# CardController.net
KiCad netlist of a schematic drawn in EAGLE
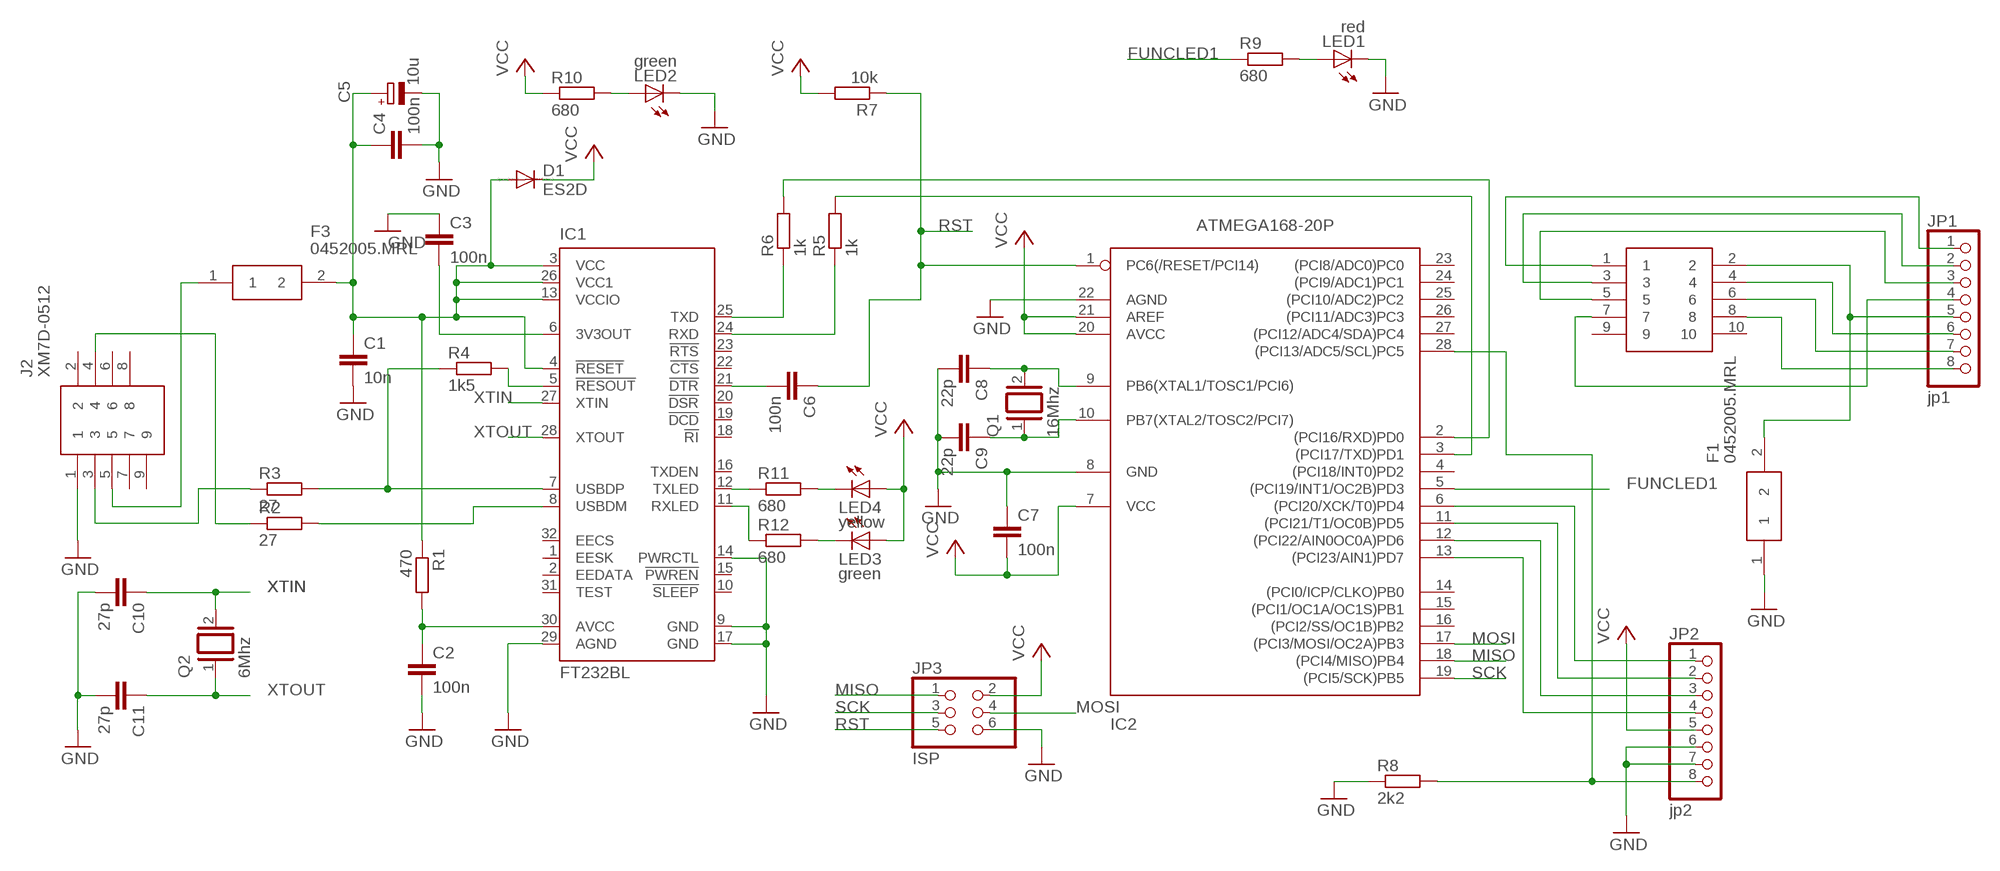
[diagram p0: schematic, sheet 1]

(export (version "E")
  (design (tool "Eeschema 10.0.6"))
  (components
    (comp (ref "C1")
      (value "10n")
      (footprint "eagle-import:C1206")
      (libsource (lib "eagle-import") (part "C-EUC1206"))
    )
    (comp (ref "C2")
      (value "100n")
      (footprint "eagle-import:C1206")
      (libsource (lib "eagle-import") (part "C-EUC1206"))
    )
    (comp (ref "C3")
      (value "100n")
      (footprint "eagle-import:C1206")
      (libsource (lib "eagle-import") (part "C-EUC1206"))
    )
    (comp (ref "C4")
      (value "100n")
      (footprint "eagle-import:C1206")
      (libsource (lib "eagle-import") (part "C-EUC1206"))
    )
    (comp (ref "C5")
      (value "10u")
      (footprint "eagle-import:B_3528-21W")
      (libsource (lib "eagle-import") (part "CPOL-EUB/3528-21W"))
    )
    (comp (ref "C6")
      (value "100n")
      (footprint "eagle-import:C1206")
      (libsource (lib "eagle-import") (part "C-EUC1206"))
    )
    (comp (ref "C7")
      (value "100n")
      (footprint "eagle-import:C1206")
      (libsource (lib "eagle-import") (part "C-EUC1206"))
    )
    (comp (ref "C8")
      (value "22p")
      (footprint "eagle-import:C1206")
      (libsource (lib "eagle-import") (part "C-EUC1206"))
    )
    (comp (ref "C9")
      (value "22p")
      (footprint "eagle-import:C1206")
      (libsource (lib "eagle-import") (part "C-EUC1206"))
    )
    (comp (ref "C10")
      (value "27p")
      (footprint "eagle-import:C1206")
      (libsource (lib "eagle-import") (part "C-EUC1206"))
    )
    (comp (ref "C11")
      (value "27p")
      (footprint "eagle-import:C1206")
      (libsource (lib "eagle-import") (part "C-EUC1206"))
    )
    (comp (ref "D1")
      (value "ES2D")
      (footprint "eagle-import:SMB")
      (libsource (lib "eagle-import") (part "ES2D"))
    )
    (comp (ref "F1")
      (value "0452005.MRL")
      (footprint "eagle-import:FUSC6127X294N")
      (fields (field (name "MOUSER_PART_NUMBER") "576-0452005.MRL"))
      (libsource (lib "eagle-import") (part "0452005.MRL"))
    )
    (comp (ref "F3")
      (value "0452005.MRL")
      (footprint "eagle-import:FUSC6127X294N")
      (fields (field (name "MOUSER_PART_NUMBER") "576-0452005.MRL"))
      (libsource (lib "eagle-import") (part "0452005.MRL"))
    )
    (comp (ref "IC1")
      (value "FT232BL")
      (footprint "eagle-import:LQFP32-7X7")
      (fields (field (name "MF") "FARNELL") (field (name "MPN") "FT232BL/TR"))
      (libsource (lib "eagle-import") (part "FT232BL"))
    )
    (comp (ref "IC2")
      (value "ATMEGA168-20P")
      (footprint "eagle-import:DIL28-3")
      (libsource (lib "eagle-import") (part "ATMEGA168P-20"))
    )
    (comp (ref "J1")
      (value "615008140121")
      (footprint "eagle-import:615008140121")
      (fields (field (name "MOUSER_PART_NUMBER") "710-615008140121"))
      (libsource (lib "eagle-import") (part "615008140121"))
    )
    (comp (ref "J2")
      (value "XM7D-0512")
      (footprint "eagle-import:XM7D0512")
      (fields (field (name "MOUSER_PART_NUMBER") "653-XM7D-0512"))
      (libsource (lib "eagle-import") (part "XM7D-0512"))
    )
    (comp (ref "JP1")
      (value "jp1")
      (footprint "eagle-import:1X08")
      (libsource (lib "eagle-import") (part "PINHD-1X8"))
    )
    (comp (ref "JP2")
      (value "jp2")
      (footprint "eagle-import:1X08")
      (libsource (lib "eagle-import") (part "PINHD-1X8"))
    )
    (comp (ref "JP3")
      (value "ISP")
      (footprint "eagle-import:2X03")
      (libsource (lib "eagle-import") (part "PINHD-2X3"))
    )
    (comp (ref "LED1")
      (value "red")
      (footprint "eagle-import:SML1206")
      (libsource (lib "eagle-import") (part "LEDSML1206"))
    )
    (comp (ref "LED2")
      (value "green")
      (footprint "eagle-import:SML1206")
      (libsource (lib "eagle-import") (part "LEDSML1206"))
    )
    (comp (ref "LED3")
      (value "green")
      (footprint "eagle-import:SML1206")
      (libsource (lib "eagle-import") (part "LEDSML1206"))
    )
    (comp (ref "LED4")
      (value "yellow")
      (footprint "eagle-import:SML1206")
      (libsource (lib "eagle-import") (part "LEDSML1206"))
    )
    (comp (ref "Q1")
      (value "16Mhz")
      (footprint "eagle-import:QS")
      (libsource (lib "eagle-import") (part "XTAL/S"))
    )
    (comp (ref "Q2")
      (value "6Mhz")
      (footprint "eagle-import:QS")
      (libsource (lib "eagle-import") (part "XTAL/S"))
    )
    (comp (ref "R1")
      (value "470")
      (footprint "eagle-import:R0805")
      (libsource (lib "eagle-import") (part "R-EU_R0805"))
    )
    (comp (ref "R2")
      (value "27")
      (footprint "eagle-import:R0805")
      (libsource (lib "eagle-import") (part "R-EU_R0805"))
    )
    (comp (ref "R3")
      (value "27")
      (footprint "eagle-import:R0805")
      (libsource (lib "eagle-import") (part "R-EU_R0805"))
    )
    (comp (ref "R4")
      (value "1k5")
      (footprint "eagle-import:R0805")
      (libsource (lib "eagle-import") (part "R-EU_R0805"))
    )
    (comp (ref "R5")
      (value "1k")
      (footprint "eagle-import:R0805")
      (libsource (lib "eagle-import") (part "R-EU_R0805"))
    )
    (comp (ref "R6")
      (value "1k")
      (footprint "eagle-import:R0805")
      (libsource (lib "eagle-import") (part "R-EU_R0805"))
    )
    (comp (ref "R7")
      (value "10k")
      (footprint "eagle-import:R0805")
      (libsource (lib "eagle-import") (part "R-EU_R0805"))
    )
    (comp (ref "R8")
      (value "2k2")
      (footprint "eagle-import:R0805")
      (libsource (lib "eagle-import") (part "R-EU_R0805"))
    )
    (comp (ref "R9")
      (value "680")
      (footprint "eagle-import:R0805")
      (libsource (lib "eagle-import") (part "R-EU_R0805"))
    )
    (comp (ref "R10")
      (value "680")
      (footprint "eagle-import:R0805")
      (libsource (lib "eagle-import") (part "R-EU_R0805"))
    )
    (comp (ref "R11")
      (value "680")
      (footprint "eagle-import:R0805")
      (libsource (lib "eagle-import") (part "R-EU_R0805"))
    )
    (comp (ref "R12")
      (value "680")
      (footprint "eagle-import:R0805")
      (libsource (lib "eagle-import") (part "R-EU_R0805"))
    )
  )
  (nets
    (net (code "1") (name "/FUNCLED1") (class "Default")
      (node (ref "IC2") (pin "5") (pinfunction "(PCI19/INT1/OC2B)PD3_5") (pintype "bidirectional"))
      (node (ref "R9") (pin "1") (pinfunction "1_1") (pintype "passive"))
    )
    (net (code "2") (name "/MISO") (class "Default")
      (node (ref "IC2") (pin "18") (pinfunction "(PCI4/MISO)PB4_18") (pintype "bidirectional"))
      (node (ref "JP3") (pin "1") (pinfunction "1_1") (pintype "passive"))
    )
    (net (code "3") (name "/MOSI") (class "Default")
      (node (ref "IC2") (pin "17") (pinfunction "(PCI3/MOSI/OC2A)PB3_17") (pintype "bidirectional"))
      (node (ref "JP3") (pin "4") (pinfunction "4_4") (pintype "passive"))
    )
    (net (code "4") (name "/RST") (class "Default")
      (node (ref "C6") (pin "1") (pinfunction "1_1") (pintype "passive"))
      (node (ref "IC2") (pin "1") (pinfunction "PC6(/RESET/PCI14)_1") (pintype "bidirectional"))
      (node (ref "JP3") (pin "5") (pinfunction "5_5") (pintype "passive"))
      (node (ref "R7") (pin "1") (pinfunction "1_1") (pintype "passive"))
    )
    (net (code "5") (name "/SCK") (class "Default")
      (node (ref "IC2") (pin "19") (pinfunction "(PCI5/SCK)PB5_19") (pintype "bidirectional"))
      (node (ref "JP3") (pin "3") (pinfunction "3_3") (pintype "passive"))
    )
    (net (code "6") (name "/XTIN") (class "Default")
      (node (ref "C10") (pin "1") (pinfunction "1_1") (pintype "passive"))
      (node (ref "IC1") (pin "27") (pinfunction "XTIN_27") (pintype "input"))
      (node (ref "Q2") (pin "2") (pinfunction "2_2") (pintype "passive"))
    )
    (net (code "7") (name "/XTOUT") (class "Default")
      (node (ref "C11") (pin "1") (pinfunction "1_1") (pintype "passive"))
      (node (ref "IC1") (pin "28") (pinfunction "XTOUT_28") (pintype "output"))
      (node (ref "Q2") (pin "1") (pinfunction "1_1") (pintype "passive"))
    )
    (net (code "8") (name "GND") (class "Default")
      (node (ref "C1") (pin "2") (pinfunction "2_2") (pintype "passive"))
      (node (ref "C10") (pin "2") (pinfunction "2_2") (pintype "passive"))
      (node (ref "C11") (pin "2") (pinfunction "2_2") (pintype "passive"))
      (node (ref "C2") (pin "2") (pinfunction "2_2") (pintype "passive"))
      (node (ref "C3") (pin "1") (pinfunction "1_1") (pintype "passive"))
      (node (ref "C4") (pin "2") (pinfunction "2_2") (pintype "passive"))
      (node (ref "C5") (pin "-") (pinfunction "-_-") (pintype "passive"))
      (node (ref "C7") (pin "1") (pinfunction "1_1") (pintype "passive"))
      (node (ref "C8") (pin "2") (pinfunction "2_2") (pintype "passive"))
      (node (ref "C9") (pin "2") (pinfunction "2_2") (pintype "passive"))
      (node (ref "F1") (pin "1") (pinfunction "1_1") (pintype "bidirectional"))
      (node (ref "IC1") (pin "14") (pinfunction "PWRCTL_14") (pintype "bidirectional"))
      (node (ref "IC1") (pin "17") (pinfunction "GND_17") (pintype "power_in"))
      (node (ref "IC1") (pin "29") (pinfunction "AGND_29") (pintype "power_in"))
      (node (ref "IC1") (pin "9") (pinfunction "GND_9") (pintype "power_in"))
      (node (ref "IC2") (pin "22") (pinfunction "AGND_22") (pintype "bidirectional"))
      (node (ref "IC2") (pin "8") (pinfunction "GND_8") (pintype "bidirectional"))
      (node (ref "J2") (pin "1") (pinfunction "1_1") (pintype "bidirectional"))
      (node (ref "JP2") (pin "6") (pinfunction "6_6") (pintype "passive"))
      (node (ref "JP2") (pin "7") (pinfunction "7_7") (pintype "passive"))
      (node (ref "JP3") (pin "6") (pinfunction "6_6") (pintype "passive"))
      (node (ref "LED1") (pin "C") (pinfunction "C_C") (pintype "passive"))
      (node (ref "LED2") (pin "C") (pinfunction "C_C") (pintype "passive"))
      (node (ref "R8") (pin "1") (pinfunction "1_1") (pintype "passive"))
    )
    (net (code "9") (name "Net-(F1-Pad2)") (class "Default")
      (node (ref "F1") (pin "2") (pinfunction "2_2") (pintype "bidirectional"))
      (node (ref "J1") (pin "2") (pinfunction "2_2") (pintype "bidirectional"))
      (node (ref "JP1") (pin "5") (pinfunction "5_5") (pintype "passive"))
    )
    (net (code "10") (name "Net-(F3-Pad1)") (class "Default")
      (node (ref "F3") (pin "1") (pinfunction "1_1") (pintype "bidirectional"))
      (node (ref "J2") (pin "5") (pinfunction "5_5") (pintype "bidirectional"))
    )
    (net (code "11") (name "Net-(IC1-3V3OUT)") (class "Default")
      (node (ref "C3") (pin "2") (pinfunction "2_2") (pintype "passive"))
      (node (ref "IC1") (pin "6") (pinfunction "3V3OUT_6") (pintype "output"))
    )
    (net (code "12") (name "Net-(IC1-AVCC)") (class "Default")
      (node (ref "C2") (pin "1") (pinfunction "1_1") (pintype "passive"))
      (node (ref "IC1") (pin "30") (pinfunction "AVCC_30") (pintype "power_in"))
      (node (ref "R1") (pin "2") (pinfunction "2_2") (pintype "passive"))
    )
    (net (code "13") (name "Net-(IC1-RXD)") (class "Default")
      (node (ref "IC1") (pin "24") (pinfunction "RXD_24") (pintype "input"))
      (node (ref "R5") (pin "1") (pinfunction "1_1") (pintype "passive"))
    )
    (net (code "14") (name "Net-(IC1-RXLED)") (class "Default")
      (node (ref "IC1") (pin "11") (pinfunction "RXLED_11") (pintype "bidirectional"))
      (node (ref "R12") (pin "1") (pinfunction "1_1") (pintype "passive"))
    )
    (net (code "15") (name "Net-(IC1-TXD)") (class "Default")
      (node (ref "IC1") (pin "25") (pinfunction "TXD_25") (pintype "output"))
      (node (ref "R6") (pin "1") (pinfunction "1_1") (pintype "passive"))
    )
    (net (code "16") (name "Net-(IC1-TXLED)") (class "Default")
      (node (ref "IC1") (pin "12") (pinfunction "TXLED_12") (pintype "bidirectional"))
      (node (ref "R11") (pin "1") (pinfunction "1_1") (pintype "passive"))
    )
    (net (code "17") (name "Net-(IC1-USBDM)") (class "Default")
      (node (ref "IC1") (pin "8") (pinfunction "USBDM_8") (pintype "bidirectional"))
      (node (ref "R2") (pin "2") (pinfunction "2_2") (pintype "passive"))
    )
    (net (code "18") (name "Net-(IC1-USBDP)") (class "Default")
      (node (ref "IC1") (pin "7") (pinfunction "USBDP_7") (pintype "bidirectional"))
      (node (ref "R3") (pin "2") (pinfunction "2_2") (pintype "passive"))
      (node (ref "R4") (pin "1") (pinfunction "1_1") (pintype "passive"))
    )
    (net (code "19") (name "Net-(IC1-VCC)") (class "Default")
      (node (ref "C1") (pin "1") (pinfunction "1_1") (pintype "passive"))
      (node (ref "C4") (pin "1") (pinfunction "1_1") (pintype "passive"))
      (node (ref "C5") (pin "+") (pinfunction "+_+") (pintype "passive"))
      (node (ref "D1") (pin "A") (pinfunction "A_A") (pintype "passive"))
      (node (ref "F3") (pin "2") (pinfunction "2_2") (pintype "bidirectional"))
      (node (ref "IC1") (pin "13") (pinfunction "VCCIO_13") (pintype "power_in"))
      (node (ref "IC1") (pin "26") (pinfunction "VCC1_26") (pintype "power_in"))
      (node (ref "IC1") (pin "3") (pinfunction "VCC_3") (pintype "power_in"))
      (node (ref "IC1") (pin "4") (pinfunction "~{RESET}_4") (pintype "input"))
      (node (ref "R1") (pin "1") (pinfunction "1_1") (pintype "passive"))
    )
    (net (code "20") (name "Net-(IC1-~{DTR})") (class "Default")
      (node (ref "C6") (pin "2") (pinfunction "2_2") (pintype "passive"))
      (node (ref "IC1") (pin "21") (pinfunction "~{DTR}_21") (pintype "output"))
    )
    (net (code "21") (name "Net-(IC1-~{RESOUT})") (class "Default")
      (node (ref "IC1") (pin "5") (pinfunction "~{RESOUT}_5") (pintype "input"))
      (node (ref "R4") (pin "2") (pinfunction "2_2") (pintype "passive"))
    )
    (net (code "22") (name "Net-(IC2-(PCI13{slash}ADC5{slash}SCL)PC5)") (class "Default")
      (node (ref "IC2") (pin "28") (pinfunction "(PCI13/ADC5/SCL)PC5_28") (pintype "bidirectional"))
      (node (ref "JP2") (pin "8") (pinfunction "8_8") (pintype "passive"))
      (node (ref "R8") (pin "2") (pinfunction "2_2") (pintype "passive"))
    )
    (net (code "23") (name "Net-(IC2-(PCI16{slash}RXD)PD0)") (class "Default")
      (node (ref "IC2") (pin "2") (pinfunction "(PCI16/RXD)PD0_2") (pintype "bidirectional"))
      (node (ref "R6") (pin "2") (pinfunction "2_2") (pintype "passive"))
    )
    (net (code "24") (name "Net-(IC2-(PCI17{slash}TXD)PD1)") (class "Default")
      (node (ref "IC2") (pin "3") (pinfunction "(PCI17/TXD)PD1_3") (pintype "bidirectional"))
      (node (ref "R5") (pin "2") (pinfunction "2_2") (pintype "passive"))
    )
    (net (code "25") (name "Net-(IC2-(PCI20{slash}XCK{slash}T0)PD4)") (class "Default")
      (node (ref "IC2") (pin "6") (pinfunction "(PCI20/XCK/T0)PD4_6") (pintype "bidirectional"))
      (node (ref "JP2") (pin "1") (pinfunction "1_1") (pintype "passive"))
    )
    (net (code "26") (name "Net-(IC2-(PCI21{slash}T1{slash}OC0B)PD5)") (class "Default")
      (node (ref "IC2") (pin "11") (pinfunction "(PCI21/T1/OC0B)PD5_11") (pintype "bidirectional"))
      (node (ref "JP2") (pin "2") (pinfunction "2_2") (pintype "passive"))
    )
    (net (code "27") (name "Net-(IC2-(PCI22{slash}AIN0OC0A)PD6)") (class "Default")
      (node (ref "IC2") (pin "12") (pinfunction "(PCI22/AIN0OC0A)PD6_12") (pintype "bidirectional"))
      (node (ref "JP2") (pin "3") (pinfunction "3_3") (pintype "passive"))
    )
    (net (code "28") (name "Net-(IC2-(PCI23{slash}AIN1)PD7)") (class "Default")
      (node (ref "IC2") (pin "13") (pinfunction "(PCI23/AIN1)PD7_13") (pintype "bidirectional"))
      (node (ref "JP2") (pin "4") (pinfunction "4_4") (pintype "passive"))
    )
    (net (code "29") (name "Net-(IC2-PB6(XTAL1{slash}TOSC1{slash}PCI6))") (class "Default")
      (node (ref "C8") (pin "1") (pinfunction "1_1") (pintype "passive"))
      (node (ref "IC2") (pin "9") (pinfunction "PB6(XTAL1/TOSC1/PCI6)_9") (pintype "bidirectional"))
      (node (ref "Q1") (pin "2") (pinfunction "2_2") (pintype "passive"))
    )
    (net (code "30") (name "Net-(IC2-PB7(XTAL2{slash}TOSC2{slash}PCI7))") (class "Default")
      (node (ref "C9") (pin "1") (pinfunction "1_1") (pintype "passive"))
      (node (ref "IC2") (pin "10") (pinfunction "PB7(XTAL2/TOSC2/PCI7)_10") (pintype "bidirectional"))
      (node (ref "Q1") (pin "1") (pinfunction "1_1") (pintype "passive"))
    )
    (net (code "31") (name "Net-(J1-Pad1)") (class "Default")
      (node (ref "J1") (pin "1") (pinfunction "1_1") (pintype "bidirectional"))
      (node (ref "JP1") (pin "1") (pinfunction "1_1") (pintype "passive"))
    )
    (net (code "32") (name "Net-(J1-Pad3)") (class "Default")
      (node (ref "J1") (pin "3") (pinfunction "3_3") (pintype "bidirectional"))
      (node (ref "JP1") (pin "2") (pinfunction "2_2") (pintype "passive"))
    )
    (net (code "33") (name "Net-(J1-Pad4)") (class "Default")
      (node (ref "J1") (pin "4") (pinfunction "4_4") (pintype "bidirectional"))
      (node (ref "JP1") (pin "6") (pinfunction "6_6") (pintype "passive"))
    )
    (net (code "34") (name "Net-(J1-Pad5)") (class "Default")
      (node (ref "J1") (pin "5") (pinfunction "5_5") (pintype "bidirectional"))
      (node (ref "JP1") (pin "3") (pinfunction "3_3") (pintype "passive"))
    )
    (net (code "35") (name "Net-(J1-Pad6)") (class "Default")
      (node (ref "J1") (pin "6") (pinfunction "6_6") (pintype "bidirectional"))
      (node (ref "JP1") (pin "7") (pinfunction "7_7") (pintype "passive"))
    )
    (net (code "36") (name "Net-(J1-Pad7)") (class "Default")
      (node (ref "J1") (pin "7") (pinfunction "7_7") (pintype "bidirectional"))
      (node (ref "JP1") (pin "4") (pinfunction "4_4") (pintype "passive"))
    )
    (net (code "37") (name "Net-(J1-Pad8)") (class "Default")
      (node (ref "J1") (pin "8") (pinfunction "8_8") (pintype "bidirectional"))
      (node (ref "JP1") (pin "8") (pinfunction "8_8") (pintype "passive"))
    )
    (net (code "38") (name "Net-(J2-Pad3)") (class "Default")
      (node (ref "J2") (pin "3") (pinfunction "3_3") (pintype "bidirectional"))
      (node (ref "R3") (pin "1") (pinfunction "1_1") (pintype "passive"))
    )
    (net (code "39") (name "Net-(J2-Pad4)") (class "Default")
      (node (ref "J2") (pin "4") (pinfunction "4_4") (pintype "bidirectional"))
      (node (ref "R2") (pin "1") (pinfunction "1_1") (pintype "passive"))
    )
    (net (code "40") (name "Net-(LED1-PadA)") (class "Default")
      (node (ref "LED1") (pin "A") (pinfunction "A_A") (pintype "passive"))
      (node (ref "R9") (pin "2") (pinfunction "2_2") (pintype "passive"))
    )
    (net (code "41") (name "Net-(LED2-PadA)") (class "Default")
      (node (ref "LED2") (pin "A") (pinfunction "A_A") (pintype "passive"))
      (node (ref "R10") (pin "2") (pinfunction "2_2") (pintype "passive"))
    )
    (net (code "42") (name "Net-(LED3-PadC)") (class "Default")
      (node (ref "LED3") (pin "C") (pinfunction "C_C") (pintype "passive"))
      (node (ref "R12") (pin "2") (pinfunction "2_2") (pintype "passive"))
    )
    (net (code "43") (name "Net-(LED4-PadC)") (class "Default")
      (node (ref "LED4") (pin "C") (pinfunction "C_C") (pintype "passive"))
      (node (ref "R11") (pin "2") (pinfunction "2_2") (pintype "passive"))
    )
    (net (code "44") (name "VCC") (class "Default")
      (node (ref "C7") (pin "2") (pinfunction "2_2") (pintype "passive"))
      (node (ref "D1") (pin "C") (pinfunction "C_C") (pintype "passive"))
      (node (ref "IC2") (pin "20") (pinfunction "AVCC_20") (pintype "bidirectional"))
      (node (ref "IC2") (pin "21") (pinfunction "AREF_21") (pintype "bidirectional"))
      (node (ref "IC2") (pin "7") (pinfunction "VCC_7") (pintype "bidirectional"))
      (node (ref "JP2") (pin "5") (pinfunction "5_5") (pintype "passive"))
      (node (ref "JP3") (pin "2") (pinfunction "2_2") (pintype "passive"))
      (node (ref "LED3") (pin "A") (pinfunction "A_A") (pintype "passive"))
      (node (ref "LED4") (pin "A") (pinfunction "A_A") (pintype "passive"))
      (node (ref "R10") (pin "1") (pinfunction "1_1") (pintype "passive"))
      (node (ref "R7") (pin "2") (pinfunction "2_2") (pintype "passive"))
    )
    (net (code "45") (name "unconnected-(IC1-EECS-Pad32)") (class "Default")
      (node (ref "IC1") (pin "32") (pinfunction "EECS_32") (pintype "input"))
    )
    (net (code "46") (name "unconnected-(IC1-EEDATA-Pad2)") (class "Default")
      (node (ref "IC1") (pin "2") (pinfunction "EEDATA_2") (pintype "input"))
    )
    (net (code "47") (name "unconnected-(IC1-EESK-Pad1)") (class "Default")
      (node (ref "IC1") (pin "1") (pinfunction "EESK_1") (pintype "input"))
    )
    (net (code "48") (name "unconnected-(IC1-TEST-Pad31)") (class "Default")
      (node (ref "IC1") (pin "31") (pinfunction "TEST_31") (pintype "input"))
    )
    (net (code "49") (name "unconnected-(IC1-TXDEN-Pad16)") (class "Default")
      (node (ref "IC1") (pin "16") (pinfunction "TXDEN_16") (pintype "bidirectional"))
    )
    (net (code "50") (name "unconnected-(IC1-~{CTS}-Pad22)") (class "Default")
      (node (ref "IC1") (pin "22") (pinfunction "~{CTS}_22") (pintype "input"))
    )
    (net (code "51") (name "unconnected-(IC1-~{DCD}-Pad19)") (class "Default")
      (node (ref "IC1") (pin "19") (pinfunction "~{DCD}_19") (pintype "input"))
    )
    (net (code "52") (name "unconnected-(IC1-~{DSR}-Pad20)") (class "Default")
      (node (ref "IC1") (pin "20") (pinfunction "~{DSR}_20") (pintype "input"))
    )
    (net (code "53") (name "unconnected-(IC1-~{PWREN}-Pad15)") (class "Default")
      (node (ref "IC1") (pin "15") (pinfunction "~{PWREN}_15") (pintype "bidirectional"))
    )
    (net (code "54") (name "unconnected-(IC1-~{RI}-Pad18)") (class "Default")
      (node (ref "IC1") (pin "18") (pinfunction "~{RI}_18") (pintype "input"))
    )
    (net (code "55") (name "unconnected-(IC1-~{RTS}-Pad23)") (class "Default")
      (node (ref "IC1") (pin "23") (pinfunction "~{RTS}_23") (pintype "output"))
    )
    (net (code "56") (name "unconnected-(IC1-~{SLEEP}-Pad10)") (class "Default")
      (node (ref "IC1") (pin "10") (pinfunction "~{SLEEP}_10") (pintype "input"))
    )
    (net (code "57") (name "unconnected-(IC2-(PCI0{slash}ICP{slash}CLKO)PB0-Pad14)") (class "Default")
      (node (ref "IC2") (pin "14") (pinfunction "(PCI0/ICP/CLKO)PB0_14") (pintype "bidirectional"))
    )
    (net (code "58") (name "unconnected-(IC2-(PCI1{slash}OC1A{slash}OC1S)PB1-Pad15)") (class "Default")
      (node (ref "IC2") (pin "15") (pinfunction "(PCI1/OC1A/OC1S)PB1_15") (pintype "bidirectional"))
    )
    (net (code "59") (name "unconnected-(IC2-(PCI2{slash}SS{slash}OC1B)PB2-Pad16)") (class "Default")
      (node (ref "IC2") (pin "16") (pinfunction "(PCI2/SS/OC1B)PB2_16") (pintype "bidirectional"))
    )
    (net (code "60") (name "unconnected-(IC2-(PCI8{slash}ADC0)PC0-Pad23)") (class "Default")
      (node (ref "IC2") (pin "23") (pinfunction "(PCI8/ADC0)PC0_23") (pintype "bidirectional"))
    )
    (net (code "61") (name "unconnected-(IC2-(PCI9{slash}ADC1)PC1-Pad24)") (class "Default")
      (node (ref "IC2") (pin "24") (pinfunction "(PCI9/ADC1)PC1_24") (pintype "bidirectional"))
    )
    (net (code "62") (name "unconnected-(IC2-(PCI10{slash}ADC2)PC2-Pad25)") (class "Default")
      (node (ref "IC2") (pin "25") (pinfunction "(PCI10/ADC2)PC2_25") (pintype "bidirectional"))
    )
    (net (code "63") (name "unconnected-(IC2-(PCI11{slash}ADC3)PC3-Pad26)") (class "Default")
      (node (ref "IC2") (pin "26") (pinfunction "(PCI11/ADC3)PC3_26") (pintype "bidirectional"))
    )
    (net (code "64") (name "unconnected-(IC2-(PCI12{slash}ADC4{slash}SDA)PC4-Pad27)") (class "Default")
      (node (ref "IC2") (pin "27") (pinfunction "(PCI12/ADC4/SDA)PC4_27") (pintype "bidirectional"))
    )
    (net (code "65") (name "unconnected-(IC2-(PCI18{slash}INT0)PD2-Pad4)") (class "Default")
      (node (ref "IC2") (pin "4") (pinfunction "(PCI18/INT0)PD2_4") (pintype "bidirectional"))
    )
    (net (code "66") (name "unconnected-(J1-Pad9)") (class "Default")
      (node (ref "J1") (pin "9") (pinfunction "9_9") (pintype "bidirectional"))
    )
    (net (code "67") (name "unconnected-(J1-Pad10)") (class "Default")
      (node (ref "J1") (pin "10") (pinfunction "10_10") (pintype "bidirectional"))
    )
    (net (code "68") (name "unconnected-(J2-Pad2)") (class "Default")
      (node (ref "J2") (pin "2") (pinfunction "2_2") (pintype "bidirectional"))
    )
    (net (code "69") (name "unconnected-(J2-Pad6)") (class "Default")
      (node (ref "J2") (pin "6") (pinfunction "6_6") (pintype "bidirectional"))
    )
    (net (code "70") (name "unconnected-(J2-Pad7)") (class "Default")
      (node (ref "J2") (pin "7") (pinfunction "7_7") (pintype "bidirectional"))
    )
    (net (code "71") (name "unconnected-(J2-Pad8)") (class "Default")
      (node (ref "J2") (pin "8") (pinfunction "8_8") (pintype "bidirectional"))
    )
    (net (code "72") (name "unconnected-(J2-Pad9)") (class "Default")
      (node (ref "J2") (pin "9") (pinfunction "9_9") (pintype "bidirectional"))
    )
  )
)
